# Glider.net
KiCad netlist of a schematic drawn in EAGLE
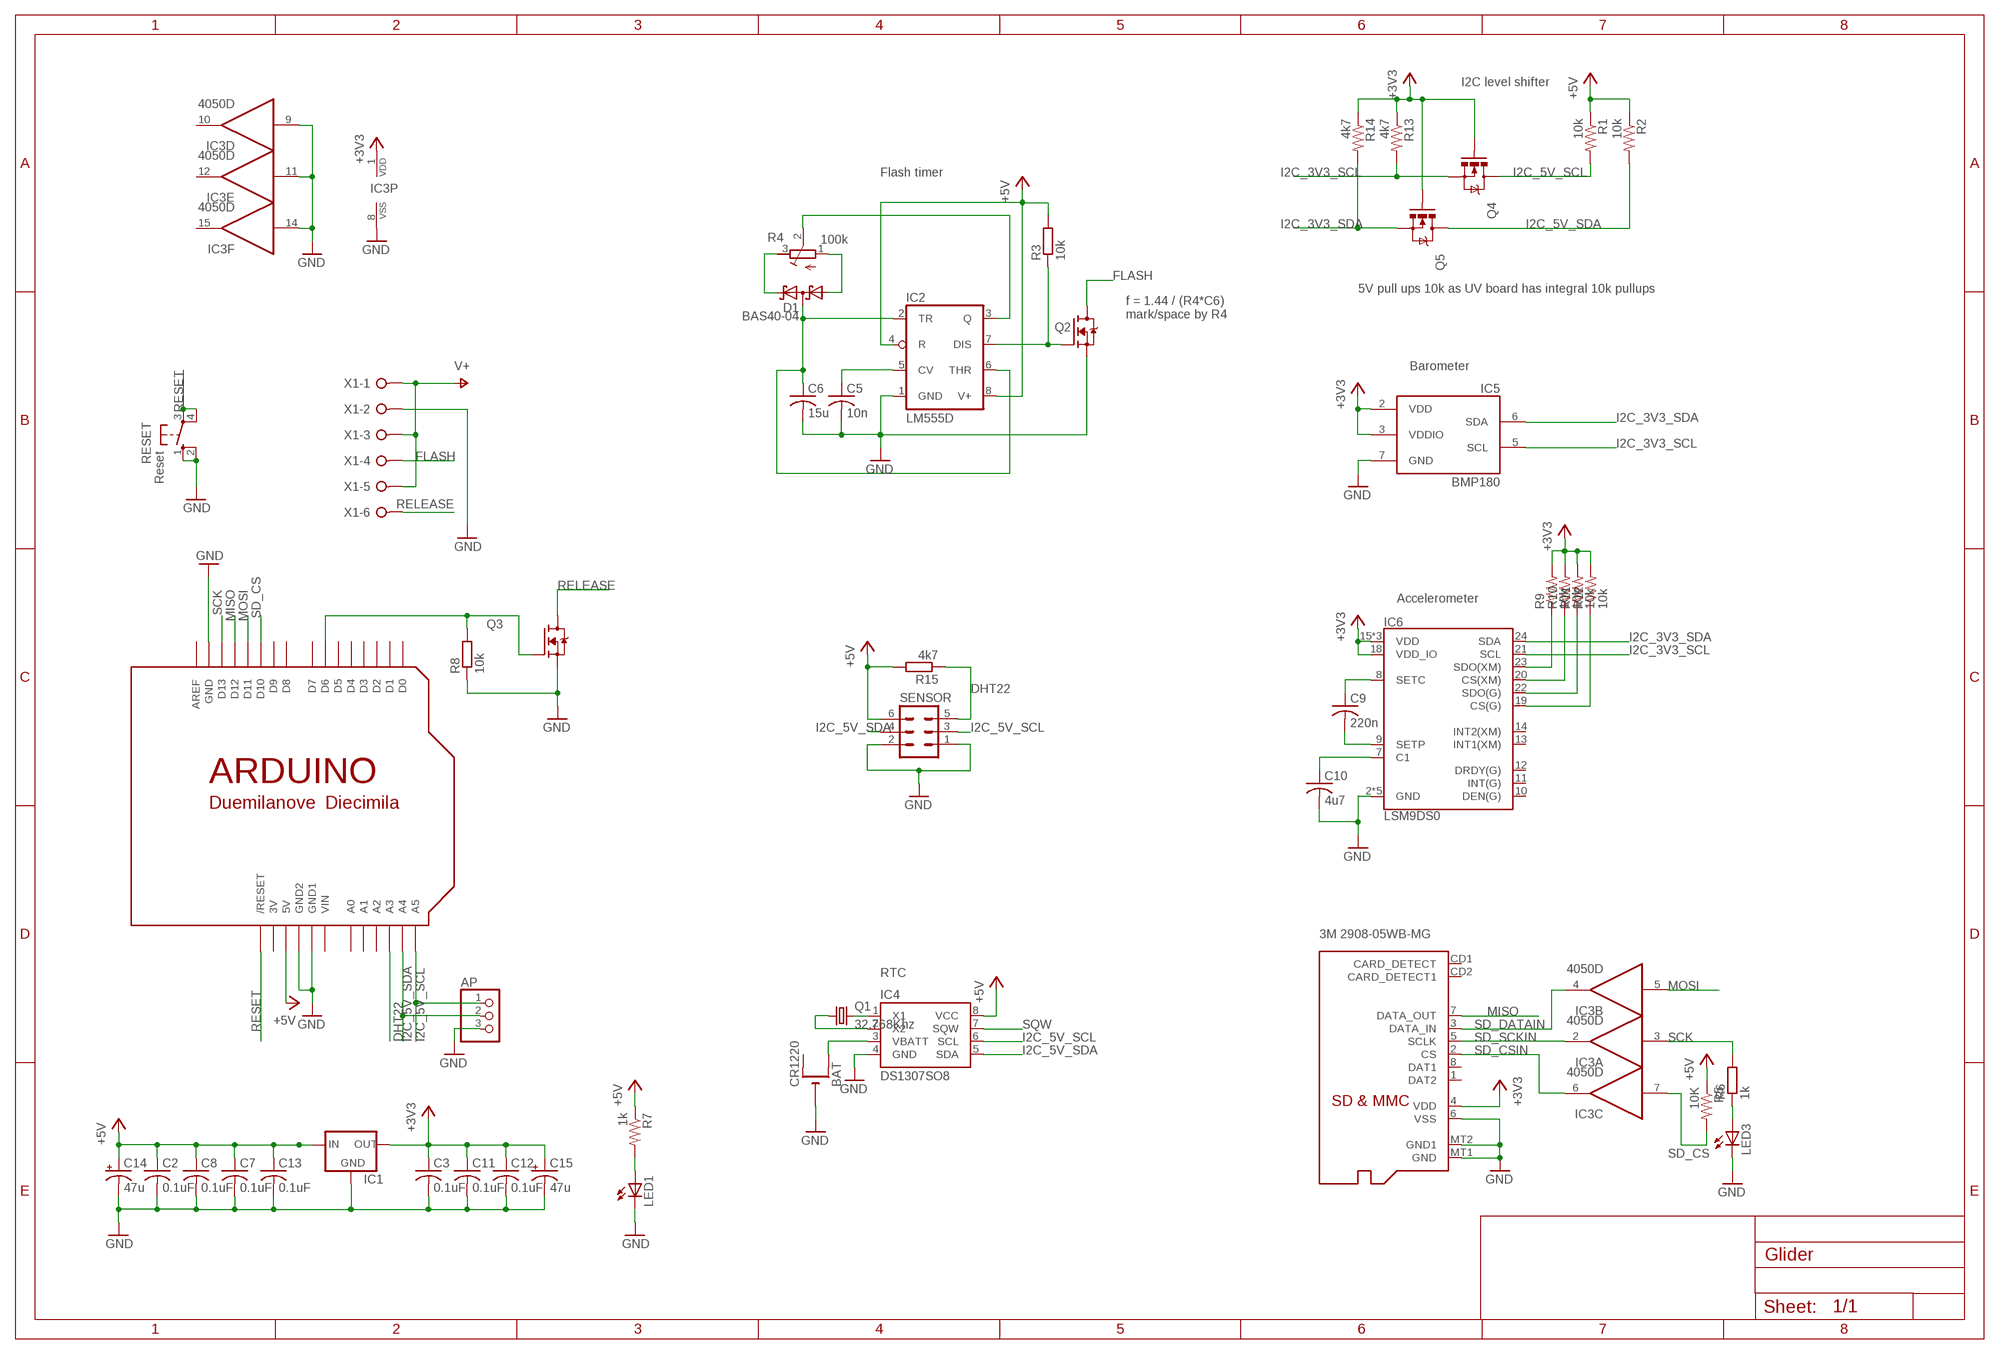
[diagram p0: schematic, sheet 1]

(export (version "E")
  (design (tool "Eeschema 10.0.6"))
  (components
    (comp (ref "AP")
      (value "PINHD-1X3")
      (footprint "eagle-import:1X03")
      (libsource (lib "eagle-import") (part "PINHD-1X3"))
    )
    (comp (ref "BAT")
      (value "CR1220")
      (footprint "eagle-import:CR1220-THM")
      (libsource (lib "eagle-import") (part "CR1220THM"))
    )
    (comp (ref "C2")
      (value "0.1uF")
      (footprint "eagle-import:C0805")
      (libsource (lib "eagle-import") (part "C-USC0805"))
    )
    (comp (ref "C3")
      (value "0.1uF")
      (footprint "eagle-import:C0805")
      (libsource (lib "eagle-import") (part "C-USC0805"))
    )
    (comp (ref "C5")
      (value "10n")
      (footprint "eagle-import:C0805")
      (libsource (lib "eagle-import") (part "rcl_C-USC0805"))
    )
    (comp (ref "C6")
      (value "15u")
      (footprint "eagle-import:C0805")
      (libsource (lib "eagle-import") (part "rcl_C-USC0805"))
    )
    (comp (ref "C7")
      (value "0.1uF")
      (footprint "eagle-import:C0805")
      (libsource (lib "eagle-import") (part "C-USC0805"))
    )
    (comp (ref "C8")
      (value "0.1uF")
      (footprint "eagle-import:C0805")
      (libsource (lib "eagle-import") (part "C-USC0805"))
    )
    (comp (ref "C9")
      (value "220n")
      (footprint "eagle-import:C0603")
      (libsource (lib "eagle-import") (part "rcl_C-USC0603"))
    )
    (comp (ref "C10")
      (value "4u7")
      (footprint "eagle-import:C0603")
      (libsource (lib "eagle-import") (part "rcl_C-USC0603"))
    )
    (comp (ref "C11")
      (value "0.1uF")
      (footprint "eagle-import:C0805")
      (libsource (lib "eagle-import") (part "C-USC0805"))
    )
    (comp (ref "C12")
      (value "0.1uF")
      (footprint "eagle-import:C0805")
      (libsource (lib "eagle-import") (part "C-USC0805"))
    )
    (comp (ref "C13")
      (value "0.1uF")
      (footprint "eagle-import:C0805")
      (libsource (lib "eagle-import") (part "C-USC0805"))
    )
    (comp (ref "C14")
      (value "47u")
      (footprint "eagle-import:SMC_B")
      (libsource (lib "eagle-import") (part "CPOL-USSMCB"))
    )
    (comp (ref "C15")
      (value "47u")
      (footprint "eagle-import:SMC_B")
      (libsource (lib "eagle-import") (part "CPOL-USSMCB"))
    )
    (comp (ref "D1")
      (value "BAS40-04")
      (footprint "eagle-import:SOT23")
      (libsource (lib "eagle-import") (part "BAS40-04"))
    )
    (comp (ref "IC1")
      (value "MCP1700TT")
      (footprint "eagle-import:SOT-23")
      (libsource (lib "eagle-import") (part "MCP1700TT"))
    )
    (comp (ref "IC2")
      (value "LM555D")
      (footprint "eagle-import:SO08")
      (libsource (lib "eagle-import") (part "555DLM"))
    )
    (comp (ref "IC3")
      (value "4050D")
      (footprint "eagle-import:SO16")
      (libsource (lib "eagle-import") (part "4050D"))
    )
    (comp (ref "IC4")
      (value "DS1307SO8")
      (footprint "eagle-import:SO08")
      (libsource (lib "eagle-import") (part "DS1307SO8"))
    )
    (comp (ref "IC5")
      (value "BMP180")
      (footprint "eagle-import:BMP180")
      (libsource (lib "eagle-import") (part "BMP180"))
    )
    (comp (ref "IC6")
      (value "LSM9DS0")
      (footprint "eagle-import:LGA-24")
      (libsource (lib "eagle-import") (part "LSM9DS0"))
    )
    (comp (ref "LED1")
      (value "LEDCHIPLED_0805")
      (footprint "eagle-import:CHIPLED_0805")
      (libsource (lib "eagle-import") (part "LEDCHIPLED_0805"))
    )
    (comp (ref "LED3")
      (value "LEDCHIPLED_0805")
      (footprint "eagle-import:CHIPLED_0805")
      (libsource (lib "eagle-import") (part "LEDCHIPLED_0805"))
    )
    (comp (ref "Q1")
      (value "32.768Khz")
      (footprint "eagle-import:TC38H")
      (libsource (lib "eagle-import") (part "CRYSTALTC38H"))
    )
    (comp (ref "Q2")
      (value "NTD20N06LT4G")
      (footprint "eagle-import:TO252")
      (libsource (lib "eagle-import") (part "NTD20N06LT4G"))
    )
    (comp (ref "Q3")
      (value "NTD20N06LT4G")
      (footprint "eagle-import:TO252")
      (libsource (lib "eagle-import") (part "NTD20N06LT4G"))
    )
    (comp (ref "Q4")
      (value "MOSFET-NCHANNELBSS123LT1G")
      (footprint "eagle-import:SOT23-3")
      (libsource (lib "eagle-import") (part "MOSFET-NCHANNELBSS123LT1G"))
    )
    (comp (ref "Q5")
      (value "MOSFET-NCHANNELBSS123LT1G")
      (footprint "eagle-import:SOT23-3")
      (libsource (lib "eagle-import") (part "MOSFET-NCHANNELBSS123LT1G"))
    )
    (comp (ref "R1")
      (value "10k")
      (footprint "eagle-import:R0805")
      (libsource (lib "eagle-import") (part "R-US_R0805"))
    )
    (comp (ref "R2")
      (value "10k")
      (footprint "eagle-import:R0805")
      (libsource (lib "eagle-import") (part "R-US_R0805"))
    )
    (comp (ref "R3")
      (value "10k")
      (footprint "eagle-import:R0805")
      (libsource (lib "eagle-import") (part "R-EU_R0805"))
    )
    (comp (ref "R4")
      (value "100k")
      (footprint "eagle-import:RTRIM3214W")
      (libsource (lib "eagle-import") (part "R-TRIMM3214W"))
    )
    (comp (ref "R5")
      (value "10K")
      (footprint "eagle-import:R0805")
      (libsource (lib "eagle-import") (part "R-US_R0805"))
    )
    (comp (ref "R6")
      (value "1k")
      (footprint "eagle-import:R0805")
      (libsource (lib "eagle-import") (part "R-EU_R0805"))
    )
    (comp (ref "R7")
      (value "1k")
      (footprint "eagle-import:R0805")
      (libsource (lib "eagle-import") (part "R-US_R0805"))
    )
    (comp (ref "R8")
      (value "10k")
      (footprint "eagle-import:R0805")
      (libsource (lib "eagle-import") (part "R-EU_R0805"))
    )
    (comp (ref "R9")
      (value "10k")
      (footprint "eagle-import:R0805")
      (libsource (lib "eagle-import") (part "rcl_R-US_R0805"))
    )
    (comp (ref "R10")
      (value "10k")
      (footprint "eagle-import:R0805")
      (libsource (lib "eagle-import") (part "rcl_R-US_R0805"))
    )
    (comp (ref "R11")
      (value "10k")
      (footprint "eagle-import:R0805")
      (libsource (lib "eagle-import") (part "rcl_R-US_R0805"))
    )
    (comp (ref "R12")
      (value "10k")
      (footprint "eagle-import:R0805")
      (libsource (lib "eagle-import") (part "rcl_R-US_R0805"))
    )
    (comp (ref "R13")
      (value "4k7")
      (footprint "eagle-import:R0805")
      (libsource (lib "eagle-import") (part "R-US_R0805"))
    )
    (comp (ref "R14")
      (value "4k7")
      (footprint "eagle-import:R0805")
      (libsource (lib "eagle-import") (part "R-US_R0805"))
    )
    (comp (ref "R15")
      (value "4k7")
      (footprint "eagle-import:R0805")
      (libsource (lib "eagle-import") (part "R-EU_R0805"))
    )
    (comp (ref "RESET")
      (value "Reset")
      (footprint "eagle-import:B3F-10XX")
      (libsource (lib "eagle-import") (part "10-XX"))
    )
    (comp (ref "SD")
      (value "MICROSD")
      (footprint "eagle-import:MICROSD")
      (libsource (lib "eagle-import") (part "MICROSD"))
    )
    (comp (ref "SENSOR")
      (value "ML6")
      (footprint "eagle-import:ML6")
      (libsource (lib "eagle-import") (part "ML6"))
    )
    (comp (ref "U$1")
      (value "ARDUINODUEMILANOVE-NOHOLES")
      (footprint "eagle-import:ARDUINO-NOHOLE")
      (libsource (lib "eagle-import") (part "ARDUINODUEMILANOVE-NOHOLES"))
    )
    (comp (ref "X1")
      (value "W237-06P")
      (footprint "eagle-import:W237-6P")
      (libsource (lib "eagle-import") (part "W237-06P"))
    )
  )
  (nets
    (net (code "1") (name "+3V3") (class "Default")
      (node (ref "C11") (pin "1") (pinfunction "1_1") (pintype "passive"))
      (node (ref "C12") (pin "1") (pinfunction "1_1") (pintype "passive"))
      (node (ref "C15") (pin "+") (pinfunction "+_+") (pintype "passive"))
      (node (ref "C3") (pin "1") (pinfunction "1_1") (pintype "passive"))
      (node (ref "IC1") (pin "2") (pinfunction "OUT_2") (pintype "passive"))
      (node (ref "IC3") (pin "1") (pinfunction "VDD_1") (pintype "power_in"))
      (node (ref "IC5") (pin "2") (pinfunction "VDD_2") (pintype "power_in"))
      (node (ref "IC5") (pin "3") (pinfunction "VDDIO_3") (pintype "power_in"))
      (node (ref "IC6") (pin "15") (pinfunction "VDD_15") (pintype "bidirectional"))
      (node (ref "IC6") (pin "16") (pinfunction "VDD_16") (pintype "bidirectional"))
      (node (ref "IC6") (pin "17") (pinfunction "VDD_17") (pintype "bidirectional"))
      (node (ref "IC6") (pin "18") (pinfunction "VDD_IO_18") (pintype "bidirectional"))
      (node (ref "Q4") (pin "1") (pinfunction "G_1") (pintype "passive"))
      (node (ref "Q5") (pin "1") (pinfunction "G_1") (pintype "passive"))
      (node (ref "R10") (pin "2") (pinfunction "2_2") (pintype "passive"))
      (node (ref "R11") (pin "2") (pinfunction "2_2") (pintype "passive"))
      (node (ref "R12") (pin "2") (pinfunction "2_2") (pintype "passive"))
      (node (ref "R13") (pin "1") (pinfunction "1_1") (pintype "passive"))
      (node (ref "R14") (pin "1") (pinfunction "1_1") (pintype "passive"))
      (node (ref "R9") (pin "2") (pinfunction "2_2") (pintype "passive"))
      (node (ref "SD") (pin "4") (pinfunction "VDD_4") (pintype "power_in"))
    )
    (net (code "2") (name "+5V") (class "Default")
      (node (ref "C13") (pin "1") (pinfunction "1_1") (pintype "passive"))
      (node (ref "C14") (pin "+") (pinfunction "+_+") (pintype "passive"))
      (node (ref "C2") (pin "1") (pinfunction "1_1") (pintype "passive"))
      (node (ref "C7") (pin "1") (pinfunction "1_1") (pintype "passive"))
      (node (ref "C8") (pin "1") (pinfunction "1_1") (pintype "passive"))
      (node (ref "IC1") (pin "3") (pinfunction "IN_3") (pintype "input"))
      (node (ref "IC2") (pin "4") (pinfunction "R_4") (pintype "input"))
      (node (ref "IC2") (pin "8") (pinfunction "V+_8") (pintype "power_in"))
      (node (ref "IC4") (pin "8") (pinfunction "VCC_8") (pintype "bidirectional"))
      (node (ref "R1") (pin "1") (pinfunction "1_1") (pintype "passive"))
      (node (ref "R15") (pin "2") (pinfunction "2_2") (pintype "passive"))
      (node (ref "R2") (pin "1") (pinfunction "1_1") (pintype "passive"))
      (node (ref "R3") (pin "2") (pinfunction "2_2") (pintype "passive"))
      (node (ref "R5") (pin "1") (pinfunction "1_1") (pintype "passive"))
      (node (ref "R7") (pin "1") (pinfunction "1_1") (pintype "passive"))
      (node (ref "SENSOR") (pin "6") (pinfunction "6_6") (pintype "passive"))
      (node (ref "U$1") (pin "5V") (pinfunction "5V_5V") (pintype "power_in"))
    )
    (net (code "3") (name "/3V") (class "Default")
      (node (ref "U$1") (pin "3V") (pinfunction "3V_3V") (pintype "power_in"))
    )
    (net (code "4") (name "/DHT22") (class "Default")
      (node (ref "R15") (pin "1") (pinfunction "1_1") (pintype "passive"))
      (node (ref "SENSOR") (pin "5") (pinfunction "5_5") (pintype "passive"))
      (node (ref "U$1") (pin "A3") (pinfunction "A3_A3") (pintype "bidirectional"))
    )
    (net (code "5") (name "/FLASH") (class "Default")
      (node (ref "Q2") (pin "4") (pinfunction "D_4") (pintype "passive"))
      (node (ref "X1") (pin "4") (pinfunction "KL_4") (pintype "passive"))
    )
    (net (code "6") (name "/I2C_3V3_SCL") (class "Default")
      (node (ref "IC5") (pin "5") (pinfunction "SCL_5") (pintype "input"))
      (node (ref "IC6") (pin "21") (pinfunction "SCL_21") (pintype "bidirectional"))
      (node (ref "Q4") (pin "2") (pinfunction "S_2") (pintype "passive"))
      (node (ref "R13") (pin "2") (pinfunction "2_2") (pintype "passive"))
    )
    (net (code "7") (name "/I2C_3V3_SDA") (class "Default")
      (node (ref "IC5") (pin "6") (pinfunction "SDA_6") (pintype "bidirectional"))
      (node (ref "IC6") (pin "24") (pinfunction "SDA_24") (pintype "bidirectional"))
      (node (ref "Q5") (pin "2") (pinfunction "S_2") (pintype "passive"))
      (node (ref "R14") (pin "2") (pinfunction "2_2") (pintype "passive"))
    )
    (net (code "8") (name "/I2C_5V_SCL") (class "Default")
      (node (ref "AP") (pin "1") (pinfunction "1_1") (pintype "passive"))
      (node (ref "IC4") (pin "6") (pinfunction "SCL_6") (pintype "bidirectional"))
      (node (ref "Q4") (pin "3") (pinfunction "D_3") (pintype "passive"))
      (node (ref "R1") (pin "2") (pinfunction "2_2") (pintype "passive"))
      (node (ref "SENSOR") (pin "3") (pinfunction "3_3") (pintype "passive"))
      (node (ref "U$1") (pin "A5") (pinfunction "A5_A5") (pintype "bidirectional"))
    )
    (net (code "9") (name "/I2C_5V_SDA") (class "Default")
      (node (ref "AP") (pin "2") (pinfunction "2_2") (pintype "passive"))
      (node (ref "IC4") (pin "5") (pinfunction "SDA_5") (pintype "bidirectional"))
      (node (ref "Q5") (pin "3") (pinfunction "D_3") (pintype "passive"))
      (node (ref "R2") (pin "2") (pinfunction "2_2") (pintype "passive"))
      (node (ref "SENSOR") (pin "4") (pinfunction "4_4") (pintype "passive"))
      (node (ref "U$1") (pin "A4") (pinfunction "A4_A4") (pintype "bidirectional"))
    )
    (net (code "10") (name "/MISO") (class "Default")
      (node (ref "SD") (pin "7") (pinfunction "DATA_OUT_7") (pintype "output"))
      (node (ref "U$1") (pin "D12") (pinfunction "D12_D12") (pintype "bidirectional"))
    )
    (net (code "11") (name "/MOSI") (class "Default")
      (node (ref "IC3") (pin "5") (pinfunction "I_5") (pintype "input"))
      (node (ref "U$1") (pin "D11") (pinfunction "D11_D11") (pintype "bidirectional"))
    )
    (net (code "12") (name "/RELEASE") (class "Default")
      (node (ref "Q3") (pin "4") (pinfunction "D_4") (pintype "passive"))
      (node (ref "X1") (pin "6") (pinfunction "KL_6") (pintype "passive"))
    )
    (net (code "13") (name "/RESET") (class "Default")
      (node (ref "RESET") (pin "3") (pinfunction "P_3") (pintype "passive"))
      (node (ref "RESET") (pin "4") (pinfunction "P1_4") (pintype "passive"))
      (node (ref "U$1") (pin "RESET") (pinfunction "/RESET_RESET") (pintype "bidirectional"))
    )
    (net (code "14") (name "/SCK") (class "Default")
      (node (ref "IC3") (pin "3") (pinfunction "I_3") (pintype "input"))
      (node (ref "R6") (pin "2") (pinfunction "2_2") (pintype "passive"))
      (node (ref "U$1") (pin "D13") (pinfunction "D13_D13") (pintype "bidirectional"))
    )
    (net (code "15") (name "/SD_CS") (class "Default")
      (node (ref "IC3") (pin "7") (pinfunction "I_7") (pintype "input"))
      (node (ref "R5") (pin "2") (pinfunction "2_2") (pintype "passive"))
      (node (ref "U$1") (pin "D10") (pinfunction "D10_D10") (pintype "bidirectional"))
    )
    (net (code "16") (name "/SD_CSIN") (class "Default")
      (node (ref "IC3") (pin "6") (pinfunction "O_6") (pintype "output"))
      (node (ref "SD") (pin "2") (pinfunction "CS_2") (pintype "input"))
    )
    (net (code "17") (name "/SD_DATAIN") (class "Default")
      (node (ref "IC3") (pin "4") (pinfunction "O_4") (pintype "output"))
      (node (ref "SD") (pin "3") (pinfunction "DATA_IN_3") (pintype "input"))
    )
    (net (code "18") (name "/SD_SCKIN") (class "Default")
      (node (ref "IC3") (pin "2") (pinfunction "O_2") (pintype "output"))
      (node (ref "SD") (pin "5") (pinfunction "SCLK_5") (pintype "input"))
    )
    (net (code "19") (name "/SQW") (class "Default")
      (node (ref "IC4") (pin "7") (pinfunction "SQW_7") (pintype "bidirectional"))
    )
    (net (code "20") (name "/VIN") (class "Default")
      (node (ref "U$1") (pin "VIN") (pinfunction "VIN_VIN") (pintype "power_in"))
    )
    (net (code "21") (name "GND") (class "Default")
      (node (ref "AP") (pin "3") (pinfunction "3_3") (pintype "passive"))
      (node (ref "BAT") (pin "-") (pinfunction "-_-") (pintype "passive"))
      (node (ref "C10") (pin "2") (pinfunction "2_2") (pintype "passive"))
      (node (ref "C11") (pin "2") (pinfunction "2_2") (pintype "passive"))
      (node (ref "C12") (pin "2") (pinfunction "2_2") (pintype "passive"))
      (node (ref "C13") (pin "2") (pinfunction "2_2") (pintype "passive"))
      (node (ref "C14") (pin "-") (pinfunction "-_-") (pintype "passive"))
      (node (ref "C15") (pin "-") (pinfunction "-_-") (pintype "passive"))
      (node (ref "C2") (pin "2") (pinfunction "2_2") (pintype "passive"))
      (node (ref "C3") (pin "2") (pinfunction "2_2") (pintype "passive"))
      (node (ref "C5") (pin "2") (pinfunction "2_2") (pintype "passive"))
      (node (ref "C6") (pin "2") (pinfunction "2_2") (pintype "passive"))
      (node (ref "C7") (pin "2") (pinfunction "2_2") (pintype "passive"))
      (node (ref "C8") (pin "2") (pinfunction "2_2") (pintype "passive"))
      (node (ref "IC1") (pin "1") (pinfunction "GND_1") (pintype "input"))
      (node (ref "IC2") (pin "1") (pinfunction "GND_1") (pintype "power_in"))
      (node (ref "IC3") (pin "11") (pinfunction "I_11") (pintype "input"))
      (node (ref "IC3") (pin "14") (pinfunction "I_14") (pintype "input"))
      (node (ref "IC3") (pin "8") (pinfunction "VSS_8") (pintype "power_in"))
      (node (ref "IC3") (pin "9") (pinfunction "I_9") (pintype "input"))
      (node (ref "IC4") (pin "4") (pinfunction "GND_4") (pintype "bidirectional"))
      (node (ref "IC5") (pin "7") (pinfunction "GND_7") (pintype "power_in"))
      (node (ref "IC6") (pin "2") (pinfunction "GND_2") (pintype "bidirectional"))
      (node (ref "IC6") (pin "3") (pinfunction "GND_3") (pintype "bidirectional"))
      (node (ref "IC6") (pin "4") (pinfunction "GND_4") (pintype "bidirectional"))
      (node (ref "IC6") (pin "5") (pinfunction "GND_5") (pintype "bidirectional"))
      (node (ref "IC6") (pin "6") (pinfunction "GND_6") (pintype "bidirectional"))
      (node (ref "LED1") (pin "C") (pinfunction "C_C") (pintype "passive"))
      (node (ref "LED3") (pin "C") (pinfunction "C_C") (pintype "passive"))
      (node (ref "Q2") (pin "3") (pinfunction "S_3") (pintype "passive"))
      (node (ref "Q3") (pin "3") (pinfunction "S_3") (pintype "passive"))
      (node (ref "R8") (pin "1") (pinfunction "1_1") (pintype "passive"))
      (node (ref "RESET") (pin "1") (pinfunction "S_1") (pintype "passive"))
      (node (ref "RESET") (pin "2") (pinfunction "S1_2") (pintype "passive"))
      (node (ref "SD") (pin "6") (pinfunction "VSS_6") (pintype "power_in"))
      (node (ref "SD") (pin "MT1") (pinfunction "GND_MT1") (pintype "power_in"))
      (node (ref "SD") (pin "MT2") (pinfunction "GND1_MT2") (pintype "power_in"))
      (node (ref "SENSOR") (pin "1") (pinfunction "1_1") (pintype "passive"))
      (node (ref "SENSOR") (pin "2") (pinfunction "2_2") (pintype "passive"))
      (node (ref "U$1") (pin "GND") (pinfunction "GND_GND") (pintype "power_in"))
      (node (ref "U$1") (pin "GND1") (pinfunction "GND1_GND1") (pintype "power_in"))
      (node (ref "U$1") (pin "GND2") (pinfunction "GND2_GND2") (pintype "power_in"))
      (node (ref "X1") (pin "2") (pinfunction "KL_2") (pintype "passive"))
    )
    (net (code "22") (name "Net-(BAT-+)") (class "Default")
      (node (ref "BAT") (pin "+1") (pinfunction "+_+1") (pintype "passive"))
      (node (ref "IC4") (pin "3") (pinfunction "VBATT_3") (pintype "bidirectional"))
    )
    (net (code "23") (name "Net-(D1-A1)") (class "Default")
      (node (ref "D1") (pin "1") (pinfunction "A1_1") (pintype "passive"))
      (node (ref "R4") (pin "1") (pinfunction "A_1") (pintype "passive"))
    )
    (net (code "24") (name "Net-(D1-C1A2)") (class "Default")
      (node (ref "C6") (pin "1") (pinfunction "1_1") (pintype "passive"))
      (node (ref "D1") (pin "3") (pinfunction "C1A2_3") (pintype "passive"))
      (node (ref "IC2") (pin "2") (pinfunction "TR_2") (pintype "input"))
      (node (ref "IC2") (pin "6") (pinfunction "THR_6") (pintype "input"))
    )
    (net (code "25") (name "Net-(D1-C2)") (class "Default")
      (node (ref "D1") (pin "2") (pinfunction "C2_2") (pintype "passive"))
      (node (ref "R4") (pin "3") (pinfunction "E_3") (pintype "passive"))
    )
    (net (code "26") (name "Net-(IC2-CV)") (class "Default")
      (node (ref "C5") (pin "1") (pinfunction "1_1") (pintype "passive"))
      (node (ref "IC2") (pin "5") (pinfunction "CV_5") (pintype "input"))
    )
    (net (code "27") (name "Net-(IC2-DIS)") (class "Default")
      (node (ref "IC2") (pin "7") (pinfunction "DIS_7") (pintype "input"))
      (node (ref "Q2") (pin "1") (pinfunction "G_1") (pintype "passive"))
      (node (ref "R3") (pin "1") (pinfunction "1_1") (pintype "passive"))
    )
    (net (code "28") (name "Net-(IC2-Q)") (class "Default")
      (node (ref "IC2") (pin "3") (pinfunction "Q_3") (pintype "output"))
      (node (ref "R4") (pin "2") (pinfunction "S_2") (pintype "passive"))
    )
    (net (code "29") (name "Net-(IC4-X1)") (class "Default")
      (node (ref "IC4") (pin "1") (pinfunction "X1_1") (pintype "bidirectional"))
      (node (ref "Q1") (pin "2") (pinfunction "2_2") (pintype "passive"))
    )
    (net (code "30") (name "Net-(IC4-X2)") (class "Default")
      (node (ref "IC4") (pin "2") (pinfunction "X2_2") (pintype "bidirectional"))
      (node (ref "Q1") (pin "1") (pinfunction "1_1") (pintype "passive"))
    )
    (net (code "31") (name "Net-(IC6-C1)") (class "Default")
      (node (ref "C10") (pin "1") (pinfunction "1_1") (pintype "passive"))
      (node (ref "IC6") (pin "7") (pinfunction "C1_7") (pintype "bidirectional"))
    )
    (net (code "32") (name "Net-(IC6-CS(G))") (class "Default")
      (node (ref "IC6") (pin "19") (pinfunction "CS(G)_19") (pintype "bidirectional"))
      (node (ref "R12") (pin "1") (pinfunction "1_1") (pintype "passive"))
    )
    (net (code "33") (name "Net-(IC6-CS(XM))") (class "Default")
      (node (ref "IC6") (pin "20") (pinfunction "CS(XM)_20") (pintype "bidirectional"))
      (node (ref "R10") (pin "1") (pinfunction "1_1") (pintype "passive"))
    )
    (net (code "34") (name "Net-(IC6-SDO(G))") (class "Default")
      (node (ref "IC6") (pin "22") (pinfunction "SDO(G)_22") (pintype "bidirectional"))
      (node (ref "R11") (pin "1") (pinfunction "1_1") (pintype "passive"))
    )
    (net (code "35") (name "Net-(IC6-SDO(XM))") (class "Default")
      (node (ref "IC6") (pin "23") (pinfunction "SDO(XM)_23") (pintype "bidirectional"))
      (node (ref "R9") (pin "1") (pinfunction "1_1") (pintype "passive"))
    )
    (net (code "36") (name "Net-(IC6-SETC)") (class "Default")
      (node (ref "C9") (pin "1") (pinfunction "1_1") (pintype "passive"))
      (node (ref "IC6") (pin "8") (pinfunction "SETC_8") (pintype "bidirectional"))
    )
    (net (code "37") (name "Net-(IC6-SETP)") (class "Default")
      (node (ref "C9") (pin "2") (pinfunction "2_2") (pintype "passive"))
      (node (ref "IC6") (pin "9") (pinfunction "SETP_9") (pintype "bidirectional"))
    )
    (net (code "38") (name "Net-(LED1-PadA)") (class "Default")
      (node (ref "LED1") (pin "A") (pinfunction "A_A") (pintype "passive"))
      (node (ref "R7") (pin "2") (pinfunction "2_2") (pintype "passive"))
    )
    (net (code "39") (name "Net-(LED3-PadA)") (class "Default")
      (node (ref "LED3") (pin "A") (pinfunction "A_A") (pintype "passive"))
      (node (ref "R6") (pin "1") (pinfunction "1_1") (pintype "passive"))
    )
    (net (code "40") (name "Net-(Q3-G)") (class "Default")
      (node (ref "Q3") (pin "1") (pinfunction "G_1") (pintype "passive"))
      (node (ref "R8") (pin "2") (pinfunction "2_2") (pintype "passive"))
      (node (ref "U$1") (pin "D6") (pinfunction "D6_D6") (pintype "bidirectional"))
    )
    (net (code "41") (name "V+") (class "Default")
      (node (ref "X1") (pin "1") (pinfunction "KL_1") (pintype "passive"))
      (node (ref "X1") (pin "3") (pinfunction "KL_3") (pintype "passive"))
      (node (ref "X1") (pin "5") (pinfunction "KL_5") (pintype "passive"))
    )
    (net (code "42") (name "unconnected-(BAT-+1-Pad+2)") (class "Default")
      (node (ref "BAT") (pin "+2") (pinfunction "+1_+2") (pintype "passive"))
    )
    (net (code "43") (name "unconnected-(IC3D-O-Pad10)") (class "Default")
      (node (ref "IC3") (pin "10") (pinfunction "O_10") (pintype "output"))
    )
    (net (code "44") (name "unconnected-(IC3E-O-Pad12)") (class "Default")
      (node (ref "IC3") (pin "12") (pinfunction "O_12") (pintype "output"))
    )
    (net (code "45") (name "unconnected-(IC3F-O-Pad15)") (class "Default")
      (node (ref "IC3") (pin "15") (pinfunction "O_15") (pintype "output"))
    )
    (net (code "46") (name "unconnected-(IC6-DEN(G)-Pad10)") (class "Default")
      (node (ref "IC6") (pin "10") (pinfunction "DEN(G)_10") (pintype "bidirectional"))
    )
    (net (code "47") (name "unconnected-(IC6-DRDY(G)-Pad12)") (class "Default")
      (node (ref "IC6") (pin "12") (pinfunction "DRDY(G)_12") (pintype "bidirectional"))
    )
    (net (code "48") (name "unconnected-(IC6-INT(G)-Pad11)") (class "Default")
      (node (ref "IC6") (pin "11") (pinfunction "INT(G)_11") (pintype "bidirectional"))
    )
    (net (code "49") (name "unconnected-(IC6-INT1(XM)-Pad13)") (class "Default")
      (node (ref "IC6") (pin "13") (pinfunction "INT1(XM)_13") (pintype "bidirectional"))
    )
    (net (code "50") (name "unconnected-(IC6-INT2(XM)-Pad14)") (class "Default")
      (node (ref "IC6") (pin "14") (pinfunction "INT2(XM)_14") (pintype "bidirectional"))
    )
    (net (code "51") (name "unconnected-(SD-CARD_DETECT-PadCD1)") (class "Default")
      (node (ref "SD") (pin "CD1") (pinfunction "CARD_DETECT_CD1") (pintype "passive"))
    )
    (net (code "52") (name "unconnected-(SD-CARD_DETECT1-PadCD2)") (class "Default")
      (node (ref "SD") (pin "CD2") (pinfunction "CARD_DETECT1_CD2") (pintype "passive"))
    )
    (net (code "53") (name "unconnected-(SD-DAT1-Pad8)") (class "Default")
      (node (ref "SD") (pin "8") (pinfunction "DAT1_8") (pintype "bidirectional"))
    )
    (net (code "54") (name "unconnected-(SD-DAT2-Pad1)") (class "Default")
      (node (ref "SD") (pin "1") (pinfunction "DAT2_1") (pintype "bidirectional"))
    )
    (net (code "55") (name "unconnected-(U$1-PadA0)") (class "Default")
      (node (ref "U$1") (pin "A0") (pinfunction "A0_A0") (pintype "bidirectional"))
    )
    (net (code "56") (name "unconnected-(U$1-PadA1)") (class "Default")
      (node (ref "U$1") (pin "A1") (pinfunction "A1_A1") (pintype "bidirectional"))
    )
    (net (code "57") (name "unconnected-(U$1-PadA2)") (class "Default")
      (node (ref "U$1") (pin "A2") (pinfunction "A2_A2") (pintype "bidirectional"))
    )
    (net (code "58") (name "unconnected-(U$1-PadAREF)") (class "Default")
      (node (ref "U$1") (pin "AREF") (pinfunction "AREF_AREF") (pintype "bidirectional"))
    )
    (net (code "59") (name "unconnected-(U$1-PadD0)") (class "Default")
      (node (ref "U$1") (pin "D0") (pinfunction "D0_D0") (pintype "bidirectional"))
    )
    (net (code "60") (name "unconnected-(U$1-PadD1)") (class "Default")
      (node (ref "U$1") (pin "D1") (pinfunction "D1_D1") (pintype "bidirectional"))
    )
    (net (code "61") (name "unconnected-(U$1-PadD2)") (class "Default")
      (node (ref "U$1") (pin "D2") (pinfunction "D2_D2") (pintype "bidirectional"))
    )
    (net (code "62") (name "unconnected-(U$1-PadD3)") (class "Default")
      (node (ref "U$1") (pin "D3") (pinfunction "D3_D3") (pintype "bidirectional"))
    )
    (net (code "63") (name "unconnected-(U$1-PadD4)") (class "Default")
      (node (ref "U$1") (pin "D4") (pinfunction "D4_D4") (pintype "bidirectional"))
    )
    (net (code "64") (name "unconnected-(U$1-PadD5)") (class "Default")
      (node (ref "U$1") (pin "D5") (pinfunction "D5_D5") (pintype "bidirectional"))
    )
    (net (code "65") (name "unconnected-(U$1-PadD7)") (class "Default")
      (node (ref "U$1") (pin "D7") (pinfunction "D7_D7") (pintype "bidirectional"))
    )
    (net (code "66") (name "unconnected-(U$1-PadD8)") (class "Default")
      (node (ref "U$1") (pin "D8") (pinfunction "D8_D8") (pintype "bidirectional"))
    )
    (net (code "67") (name "unconnected-(U$1-PadD9)") (class "Default")
      (node (ref "U$1") (pin "D9") (pinfunction "D9_D9") (pintype "bidirectional"))
    )
  )
)
